# RFM12B-V1_2-SMD.net
KiCad netlist of a schematic drawn in EAGLE
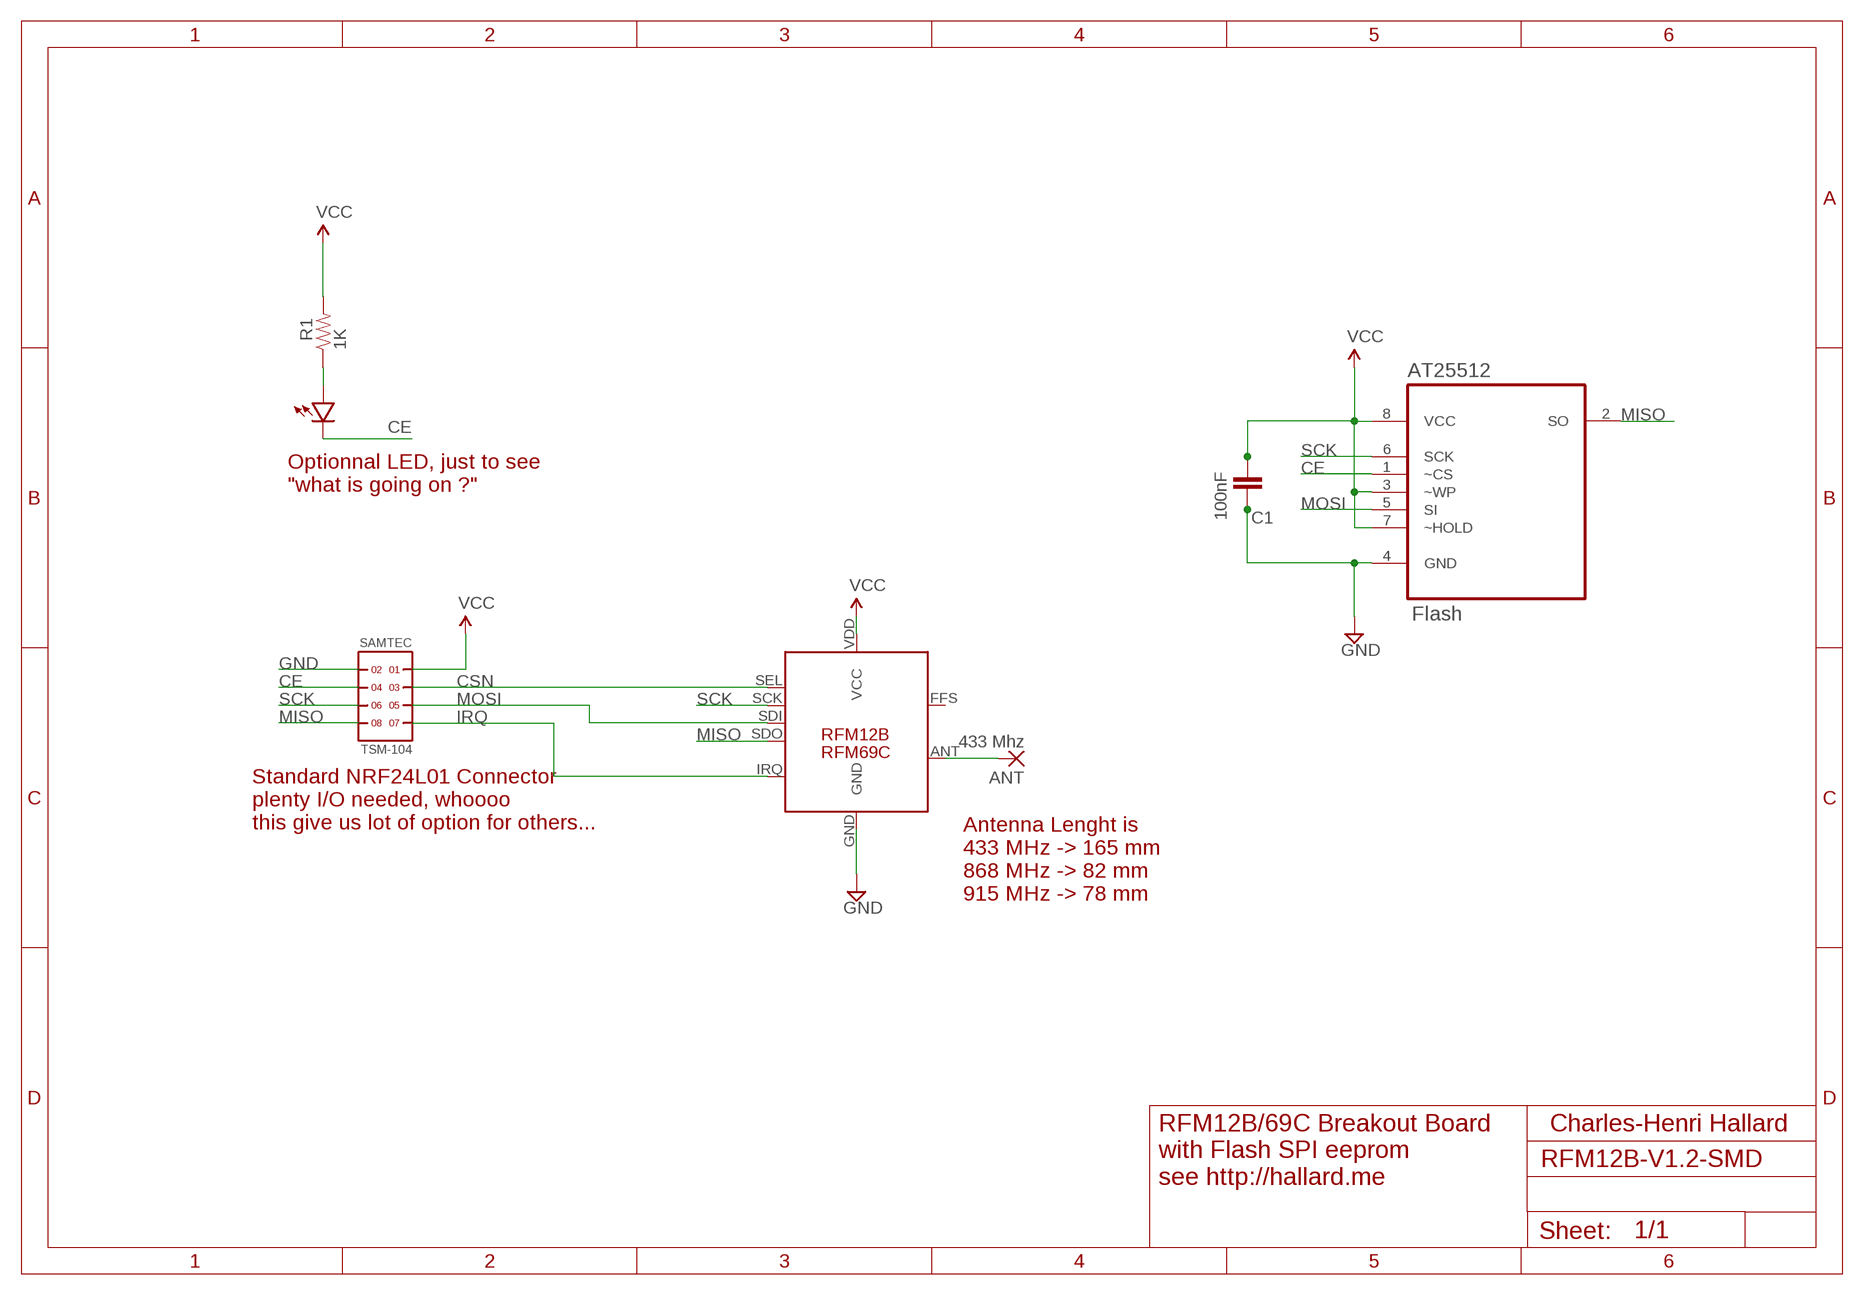
[diagram p0: schematic, sheet 1]

(export (version "E")
  (design (tool "Eeschema 10.0.6"))
  (components
    (comp (ref "ANT")
      (value "433 Mhz")
      (footprint "eagle-import:1,6_0,8")
      (libsource (lib "eagle-import") (part "1,6/0,8"))
    )
    (comp (ref "AT25512")
      (value "Flash")
      (footprint "eagle-import:SOIC127P600X175-8N")
      (fields (field (name "MPN") "AT25512N-SH-B"))
      (libsource (lib "eagle-import") (part "AT25512N-SH-B"))
    )
    (comp (ref "C1")
      (value "100nF")
      (footprint "eagle-import:0805-CAP")
      (libsource (lib "eagle-import") (part "CAP0805-CAP"))
    )
    (comp (ref "R1")
      (value "1K")
      (footprint "eagle-import:0805-RES")
      (libsource (lib "eagle-import") (part "RESISTOR0805-RES"))
    )
    (comp (ref "SAMTEC")
      (value "TSM-104")
      (footprint "eagle-import:TSM-104")
      (libsource (lib "eagle-import") (part "TSM-104"))
    )
    (comp (ref "U$2")
      (value "RFM12B")
      (footprint "eagle-import:RFM12B")
      (libsource (lib "eagle-import") (part "RFM12B"))
    )
    (comp (ref "U$3")
      (value "LED0805-LARGE")
      (footprint "eagle-import:0805-LED-LARGEPADS")
      (libsource (lib "eagle-import") (part "LED0805-LARGE"))
    )
  )
  (nets
    (net (code "1") (name "/CE") (class "Default")
      (node (ref "AT25512") (pin "1") (pinfunction "~{CS}_1") (pintype "input"))
      (node (ref "SAMTEC") (pin "4") (pinfunction "4_4") (pintype "bidirectional"))
      (node (ref "U$3") (pin "MINUS") (pinfunction "MINUS_MINUS") (pintype "passive"))
    )
    (net (code "2") (name "/CSN") (class "Default")
      (node (ref "SAMTEC") (pin "3") (pinfunction "3_3") (pintype "bidirectional"))
      (node (ref "U$2") (pin "SEL") (pinfunction "SEL_SEL") (pintype "input"))
    )
    (net (code "3") (name "/IRQ") (class "Default")
      (node (ref "SAMTEC") (pin "7") (pinfunction "7_7") (pintype "bidirectional"))
      (node (ref "U$2") (pin "IRQ") (pinfunction "IRQ_IRQ") (pintype "open_collector"))
    )
    (net (code "4") (name "/MISO") (class "Default")
      (node (ref "AT25512") (pin "2") (pinfunction "SO_2") (pintype "output"))
      (node (ref "SAMTEC") (pin "8") (pinfunction "8_8") (pintype "bidirectional"))
      (node (ref "U$2") (pin "SDO") (pinfunction "SDO_SDO") (pintype "output"))
    )
    (net (code "5") (name "/MOSI") (class "Default")
      (node (ref "AT25512") (pin "5") (pinfunction "SI_5") (pintype "input"))
      (node (ref "SAMTEC") (pin "5") (pinfunction "5_5") (pintype "bidirectional"))
      (node (ref "U$2") (pin "SDI") (pinfunction "SDI_SDI") (pintype "input"))
    )
    (net (code "6") (name "/SCK") (class "Default")
      (node (ref "AT25512") (pin "6") (pinfunction "SCK_6") (pintype "input"))
      (node (ref "SAMTEC") (pin "6") (pinfunction "6_6") (pintype "bidirectional"))
      (node (ref "U$2") (pin "SCK") (pinfunction "SCK_SCK") (pintype "input"))
    )
    (net (code "7") (name "GND") (class "Default")
      (node (ref "AT25512") (pin "4") (pinfunction "GND_4") (pintype "passive"))
      (node (ref "C1") (pin "2") (pinfunction "2_2") (pintype "passive"))
      (node (ref "SAMTEC") (pin "2") (pinfunction "2_2") (pintype "bidirectional"))
      (node (ref "U$2") (pin "GND") (pinfunction "GND_GND") (pintype "power_in"))
    )
    (net (code "8") (name "Net-(ANT-P)") (class "Default")
      (node (ref "ANT") (pin "1") (pinfunction "P_1") (pintype "passive"))
      (node (ref "U$2") (pin "ANT") (pinfunction "ANT_ANT") (pintype "passive"))
    )
    (net (code "9") (name "Net-(R1-Pad1)") (class "Default")
      (node (ref "R1") (pin "1") (pinfunction "1_1") (pintype "passive"))
      (node (ref "U$3") (pin "PLUS") (pinfunction "PLUS_PLUS") (pintype "passive"))
    )
    (net (code "10") (name "VCC") (class "Default")
      (node (ref "AT25512") (pin "3") (pinfunction "~{WP}_3") (pintype "input"))
      (node (ref "AT25512") (pin "7") (pinfunction "~{HOLD}_7") (pintype "input"))
      (node (ref "AT25512") (pin "8") (pinfunction "VCC_8") (pintype "power_in"))
      (node (ref "C1") (pin "1") (pinfunction "1_1") (pintype "passive"))
      (node (ref "R1") (pin "2") (pinfunction "2_2") (pintype "passive"))
      (node (ref "SAMTEC") (pin "1") (pinfunction "1_1") (pintype "bidirectional"))
      (node (ref "U$2") (pin "VDD") (pinfunction "VCC_VDD") (pintype "power_in"))
    )
    (net (code "11") (name "unconnected-(U$2-PadFFS)") (class "Default")
      (node (ref "U$2") (pin "FFS") (pinfunction "FFS_FFS") (pintype "bidirectional"))
    )
  )
)
